# 3_-_display.net
KiCad netlist of a schematic drawn in Altium Designer
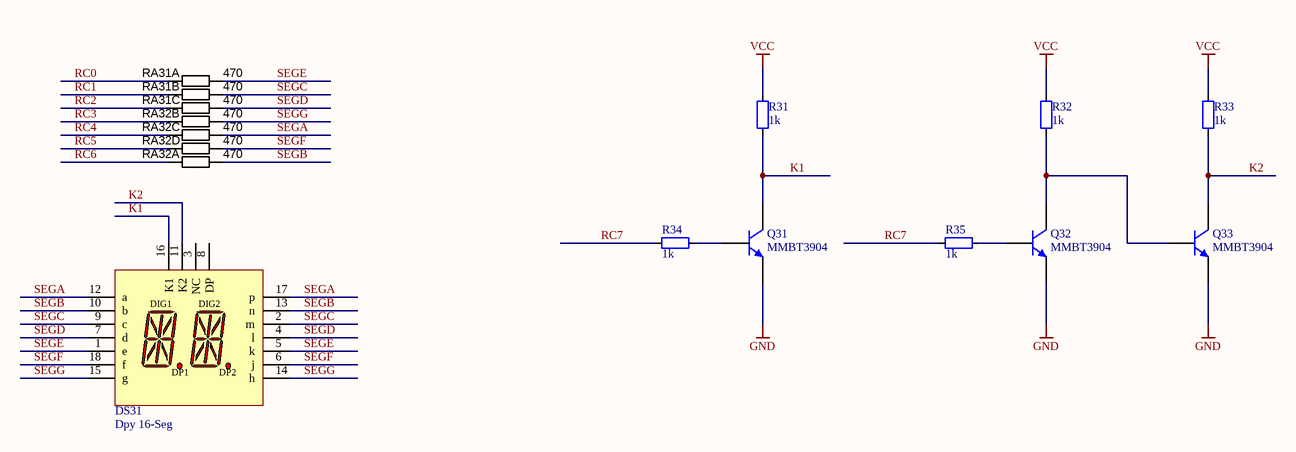
[diagram p0: 3 - display.SchDoc]

(export (version "E")
  (design (tool "Eeschema 10.0.6"))
  (components
    (comp (ref "DS31")
      (value "Dpy 16-Seg")
      (footprint "HDSP-A2")
      (description "13.7 mm Gray Surface As AlInGaP Red Alphanumeric Display: 2-Character, CC")
      (fields (field (name "PUBLISHER") "Altium Limited"))
      (libsource (lib "Miscellaneous Devices") (part "Dpy 16-Seg"))
    )
    (comp (ref "Q31")
      (value "MMBT3904")
      (footprint "SOT23_N")
      (description "NPN Switching Transistor")
      (fields (field (name "PUBLISHER") "Altium Limited"))
      (libsource (lib "Philips Discrete BJT - Low Power") (part "MMBT3904"))
    )
    (comp (ref "Q32")
      (value "MMBT3904")
      (footprint "SOT23_N")
      (description "NPN Switching Transistor")
      (fields (field (name "PUBLISHER") "Altium Limited"))
      (libsource (lib "Philips Discrete BJT - Low Power") (part "MMBT3904"))
    )
    (comp (ref "Q33")
      (value "MMBT3904")
      (footprint "SOT23_N")
      (description "NPN Switching Transistor")
      (fields (field (name "PUBLISHER") "Altium Limited"))
      (libsource (lib "Philips Discrete BJT - Low Power") (part "MMBT3904"))
    )
    (comp (ref "R31")
      (value "1k")
      (footprint "PCB_PassiveRes:RES_0603")
      (description "Resistor")
      (fields (field (name "Comment") "Res_0603"))
      (libsource (lib "SCH_Passive") (part "Res_0603"))
    )
    (comp (ref "R32")
      (value "1k")
      (footprint "PCB_PassiveRes:RES_0603")
      (description "Resistor")
      (fields (field (name "Comment") "Res_0603"))
      (libsource (lib "SCH_Passive") (part "Res_0603"))
    )
    (comp (ref "R33")
      (value "1k")
      (footprint "PCB_PassiveRes:RES_0603")
      (description "Resistor")
      (fields (field (name "Comment") "Res_0603"))
      (libsource (lib "SCH_Passive") (part "Res_0603"))
    )
    (comp (ref "R34")
      (value "1k")
      (footprint "PCB_PassiveRes:RES_0603")
      (description "Resistor")
      (fields (field (name "Comment") "Res_0603"))
      (libsource (lib "") (part "Res_0603_1"))
    )
    (comp (ref "R35")
      (value "1k")
      (footprint "PCB_PassiveRes:RES_0603")
      (description "Resistor")
      (fields (field (name "Comment") "Res_0603"))
      (libsource (lib "") (part "Res_0603_1"))
    )
    (comp (ref "RA31")
      (value "470")
      (footprint "RESCAXS50P160X320X70-8N")
      (description "Resistor array 1K Ohm 4-pack 62.5mW 5% 4x1608 SMD")
      (fields (field (name "TOLERANCE") "±5%") (field (name "Comment") "Film Res Pack"))
      (libsource (lib "PBL - Resistors") (part "RESPACK_1K_5%_4X"))
    )
    (comp (ref "RA32")
      (value "470")
      (footprint "RESCAXS50P160X320X70-8N")
      (description "Resistor array 1K Ohm 4-pack 62.5mW 5% 4x1608 SMD")
      (fields (field (name "TOLERANCE") "±5%") (field (name "Comment") "Film Res Pack"))
      (libsource (lib "PBL - Resistors") (part "RESPACK_1K_5%_4X"))
    )
  )
  (nets
    (net (code "1") (name "/K1") (class "Default")
      (node (ref "DS31") (pin "16") (pinfunction "K1_16") (pintype "passive"))
      (node (ref "Q31") (pin "3") (pinfunction "C_3") (pintype "passive"))
      (node (ref "R31") (pin "1") (pinfunction "1_1") (pintype "passive"))
    )
    (net (code "2") (name "/K2") (class "Default")
      (node (ref "DS31") (pin "11") (pinfunction "K2_11") (pintype "passive"))
      (node (ref "Q33") (pin "3") (pinfunction "C_3") (pintype "passive"))
      (node (ref "R33") (pin "1") (pinfunction "1_1") (pintype "passive"))
    )
    (net (code "3") (name "/RC0") (class "Default")
      (node (ref "RA31") (pin "1") (pinfunction "1_1") (pintype "passive"))
    )
    (net (code "4") (name "/RC1") (class "Default")
      (node (ref "RA31") (pin "2") (pinfunction "2_2") (pintype "passive"))
    )
    (net (code "5") (name "/RC2") (class "Default")
      (node (ref "RA31") (pin "3") (pinfunction "3_3") (pintype "passive"))
    )
    (net (code "6") (name "/RC3") (class "Default")
      (node (ref "RA32") (pin "2") (pinfunction "2_2") (pintype "passive"))
    )
    (net (code "7") (name "/RC4") (class "Default")
      (node (ref "RA32") (pin "3") (pinfunction "3_3") (pintype "passive"))
    )
    (net (code "8") (name "/RC5") (class "Default")
      (node (ref "RA32") (pin "4") (pinfunction "4_4") (pintype "passive"))
    )
    (net (code "9") (name "/RC6") (class "Default")
      (node (ref "RA32") (pin "1") (pinfunction "1_1") (pintype "passive"))
    )
    (net (code "10") (name "/RC7") (class "Default")
      (node (ref "R34") (pin "2") (pinfunction "2_2") (pintype "passive"))
      (node (ref "R35") (pin "2") (pinfunction "2_2") (pintype "passive"))
    )
    (net (code "11") (name "/SEGA") (class "Default")
      (node (ref "DS31") (pin "12") (pinfunction "a_12") (pintype "passive"))
      (node (ref "DS31") (pin "17") (pinfunction "p_17") (pintype "passive"))
      (node (ref "RA32") (pin "6") (pinfunction "6_6") (pintype "passive"))
    )
    (net (code "12") (name "/SEGB") (class "Default")
      (node (ref "DS31") (pin "10") (pinfunction "b_10") (pintype "passive"))
      (node (ref "DS31") (pin "13") (pinfunction "n_13") (pintype "passive"))
      (node (ref "RA32") (pin "8") (pinfunction "8_8") (pintype "passive"))
    )
    (net (code "13") (name "/SEGC") (class "Default")
      (node (ref "DS31") (pin "2") (pinfunction "m_2") (pintype "passive"))
      (node (ref "DS31") (pin "9") (pinfunction "c_9") (pintype "passive"))
      (node (ref "RA31") (pin "7") (pinfunction "7_7") (pintype "passive"))
    )
    (net (code "14") (name "/SEGD") (class "Default")
      (node (ref "DS31") (pin "4") (pinfunction "l_4") (pintype "passive"))
      (node (ref "DS31") (pin "7") (pinfunction "d_7") (pintype "passive"))
      (node (ref "RA31") (pin "6") (pinfunction "6_6") (pintype "passive"))
    )
    (net (code "15") (name "/SEGE") (class "Default")
      (node (ref "DS31") (pin "1") (pinfunction "e_1") (pintype "passive"))
      (node (ref "DS31") (pin "5") (pinfunction "k_5") (pintype "passive"))
      (node (ref "RA31") (pin "8") (pinfunction "8_8") (pintype "passive"))
    )
    (net (code "16") (name "/SEGF") (class "Default")
      (node (ref "DS31") (pin "18") (pinfunction "f_18") (pintype "passive"))
      (node (ref "DS31") (pin "6") (pinfunction "j_6") (pintype "passive"))
      (node (ref "RA32") (pin "5") (pinfunction "5_5") (pintype "passive"))
    )
    (net (code "17") (name "/SEGG") (class "Default")
      (node (ref "DS31") (pin "14") (pinfunction "h_14") (pintype "passive"))
      (node (ref "DS31") (pin "15") (pinfunction "g_15") (pintype "passive"))
      (node (ref "RA32") (pin "7") (pinfunction "7_7") (pintype "passive"))
    )
    (net (code "18") (name "GND") (class "Default")
      (node (ref "Q31") (pin "2") (pinfunction "E_2") (pintype "passive"))
      (node (ref "Q32") (pin "2") (pinfunction "E_2") (pintype "passive"))
      (node (ref "Q33") (pin "2") (pinfunction "E_2") (pintype "passive"))
    )
    (net (code "19") (name "Net-(Q31-B)") (class "Default")
      (node (ref "Q31") (pin "1") (pinfunction "B_1") (pintype "passive"))
      (node (ref "R34") (pin "1") (pinfunction "1_1") (pintype "passive"))
    )
    (net (code "20") (name "Net-(Q32-B)") (class "Default")
      (node (ref "Q32") (pin "1") (pinfunction "B_1") (pintype "passive"))
      (node (ref "R35") (pin "1") (pinfunction "1_1") (pintype "passive"))
    )
    (net (code "21") (name "Net-(Q32-C)") (class "Default")
      (node (ref "Q32") (pin "3") (pinfunction "C_3") (pintype "passive"))
      (node (ref "Q33") (pin "1") (pinfunction "B_1") (pintype "passive"))
      (node (ref "R32") (pin "1") (pinfunction "1_1") (pintype "passive"))
    )
    (net (code "22") (name "VCC") (class "Default")
      (node (ref "R31") (pin "2") (pinfunction "2_2") (pintype "passive"))
      (node (ref "R32") (pin "2") (pinfunction "2_2") (pintype "passive"))
      (node (ref "R33") (pin "2") (pinfunction "2_2") (pintype "passive"))
    )
    (net (code "23") (name "unconnected-(DS31-DP-Pad8)") (class "Default")
      (node (ref "DS31") (pin "8") (pinfunction "DP_8") (pintype "passive"))
    )
    (net (code "24") (name "unconnected-(DS31-NC-Pad3)") (class "Default")
      (node (ref "DS31") (pin "3") (pinfunction "NC_3") (pintype "passive"))
    )
  )
)
